# SCH_esp32__2024-09-23.net
KiCad netlist of a schematic drawn in EasyEDA
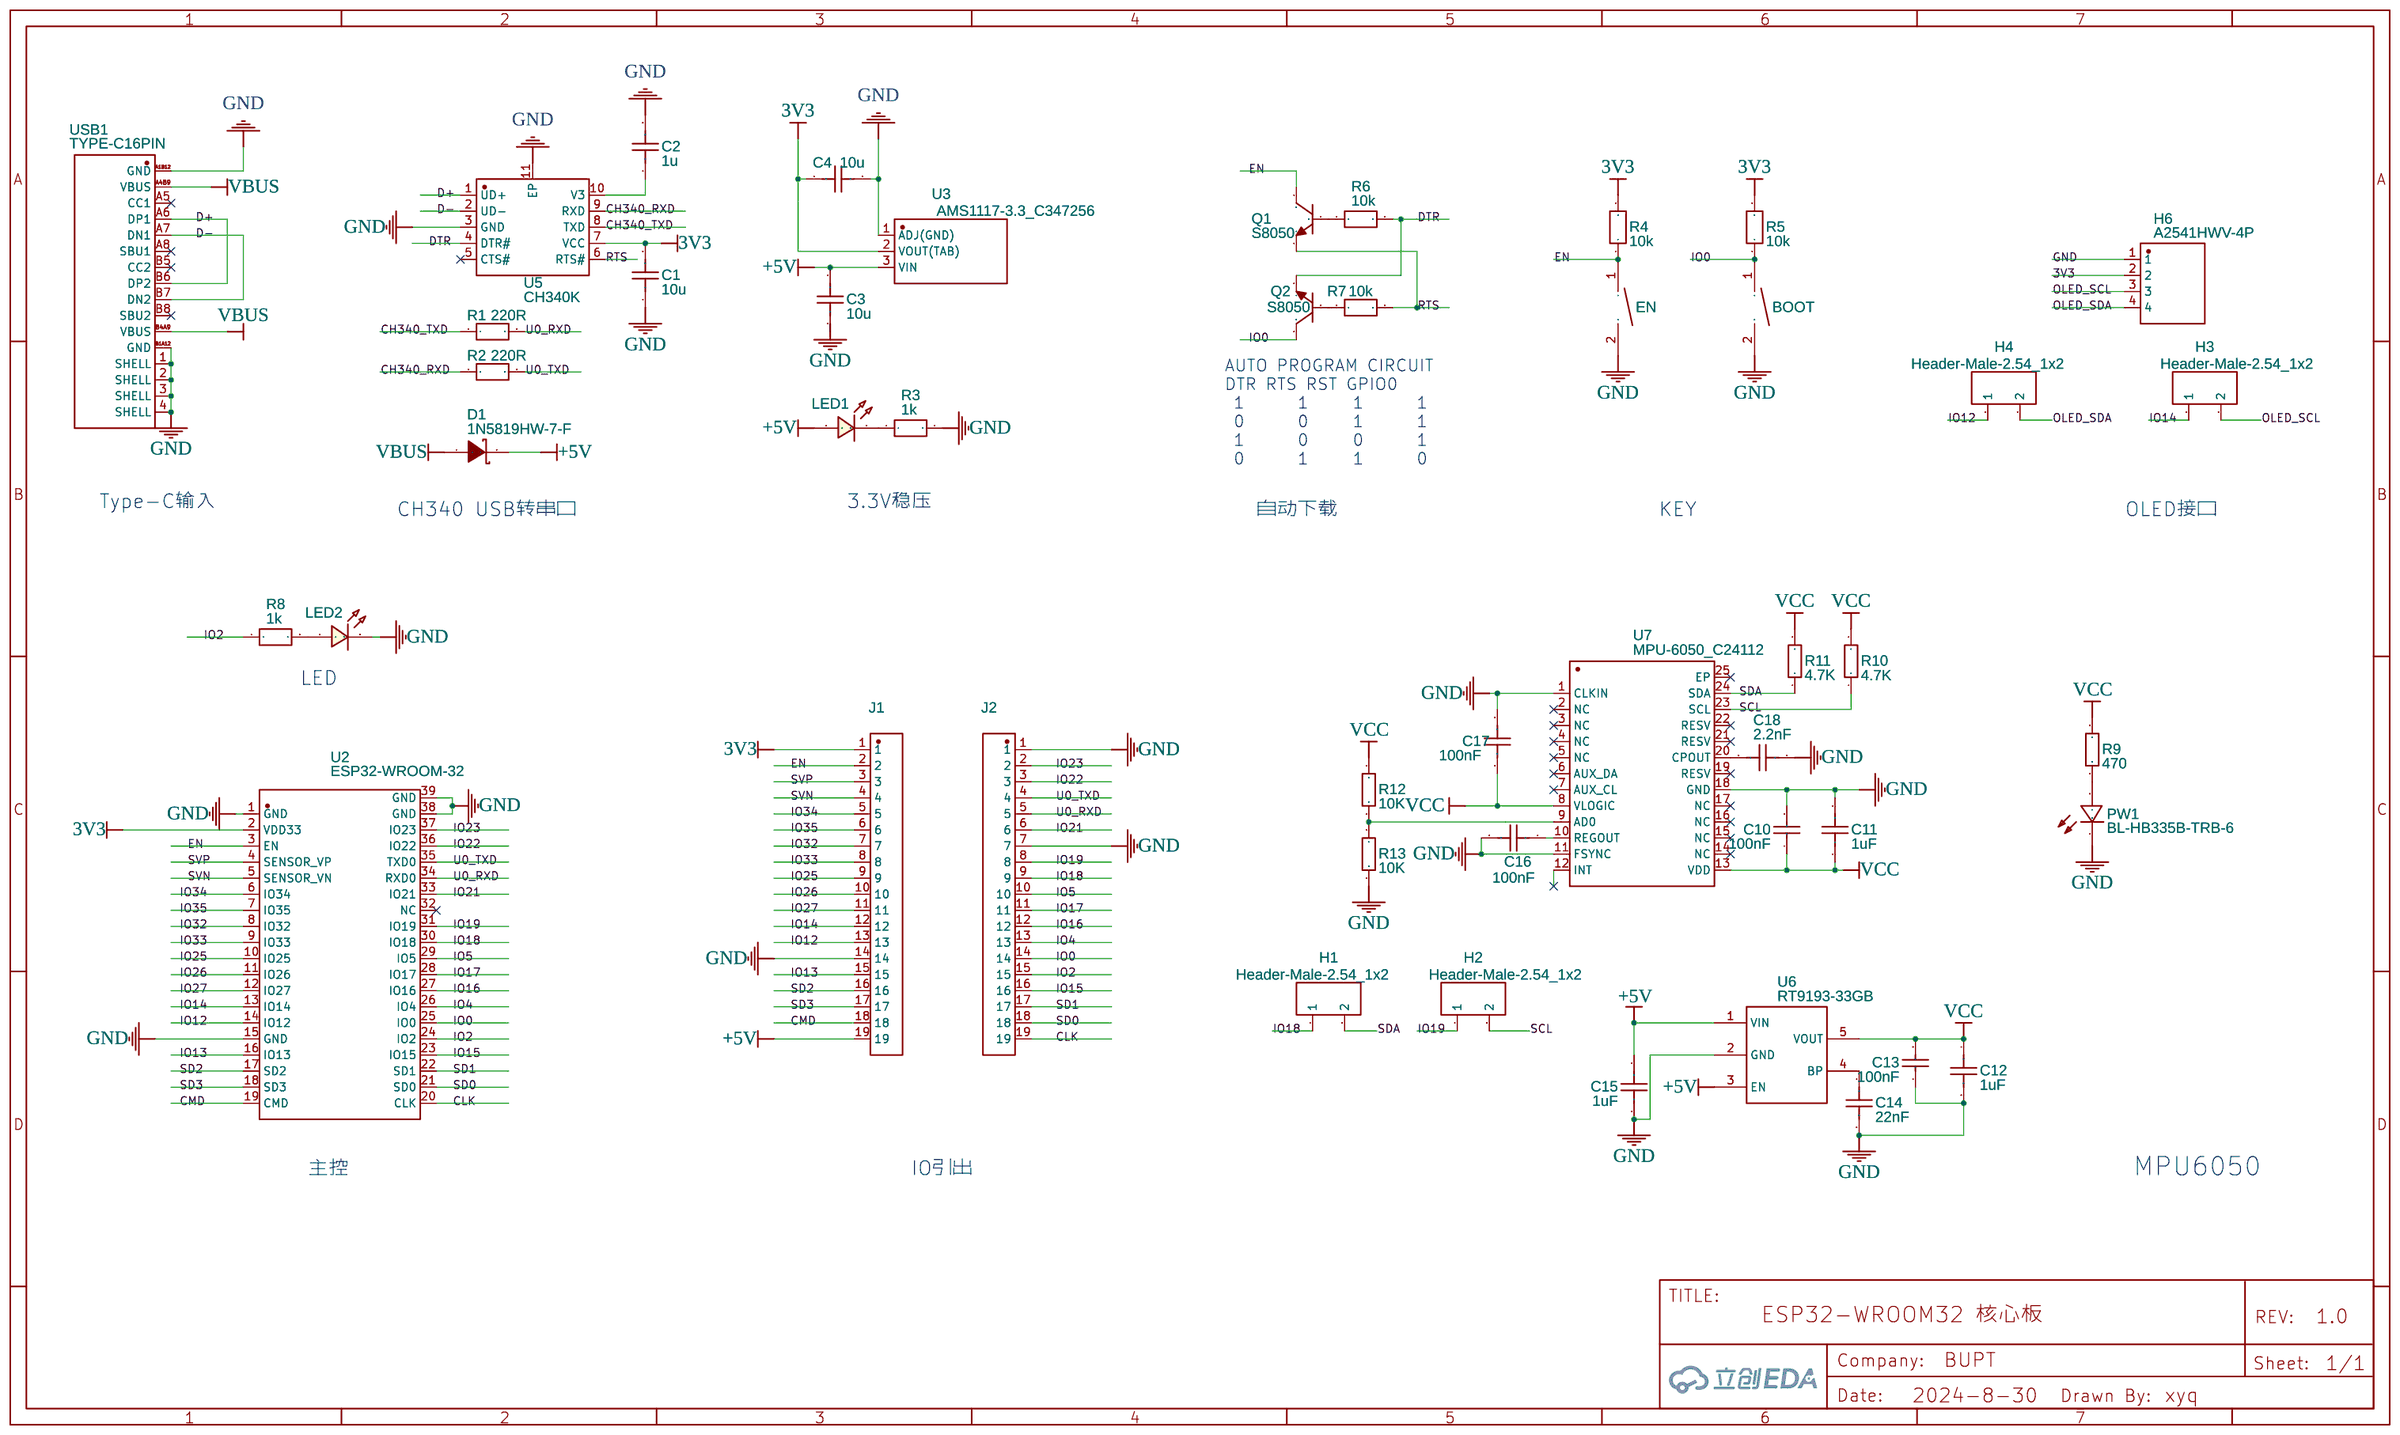
[diagram p0: schematic sheet]

(export (version "E")
  (design (tool "Eeschema 10.0.6"))
  (components
    (comp (ref "BOOT")
      (value "TSA343G00D-250J2")
      (fields (field (name "Manufacturer") "BRIGHT"))
      (libsource (lib "") (part "TSA343G00D-250J2"))
    )
    (comp (ref "C1") (value "10u") (libsource (lib "") (part "C_0603_US_1")))
    (comp (ref "C2") (value "1u") (libsource (lib "") (part "C_0603_US_1")))
    (comp (ref "C3") (value "10u") (libsource (lib "") (part "C_0603_US_2")))
    (comp (ref "C4") (value "10u") (libsource (lib "") (part "C_0603_US")))
    (comp (ref "C10")
      (value "100nF")
      (fields
        (field (name "Manufacturer Part") "CT41G-0603-2X1-50V-0.1μF-K(N)")
        (field (name "Manufacturer") "TORCH")
      )
      (libsource (lib "") (part "CT41G-0603-2X1-50V-0.1μF-K(N)"))
    )
    (comp (ref "C11")
      (value "1uF")
      (fields
        (field (name "Manufacturer Part") "GRM185R61E105KA12D")
        (field (name "Manufacturer") "Murata Electronics")
      )
      (libsource (lib "") (part "GRM185R61E105KA12D_1"))
    )
    (comp (ref "C12")
      (value "1uF")
      (fields
        (field (name "Manufacturer Part") "GRM185R61E105KA12D")
        (field (name "Manufacturer") "Murata Electronics")
      )
      (libsource (lib "") (part "GRM185R61E105KA12D_1"))
    )
    (comp (ref "C13")
      (value "100nF")
      (fields
        (field (name "Manufacturer Part") "CT41G-0603-2X1-50V-0.1μF-K(N)")
        (field (name "Manufacturer") "TORCH")
      )
      (libsource (lib "") (part "CT41G-0603-2X1-50V-0.1μF-K(N)"))
    )
    (comp (ref "C14")
      (value "22nF")
      (fields
        (field (name "Manufacturer Part") "0603B223K500CT")
        (field (name "Manufacturer") "Walsin Tech Corp")
      )
      (libsource (lib "") (part "0603B223K500CT"))
    )
    (comp (ref "C15")
      (value "1uF")
      (fields
        (field (name "Manufacturer Part") "GRM185R61E105KA12D")
        (field (name "Manufacturer") "Murata Electronics")
      )
      (libsource (lib "") (part "GRM185R61E105KA12D"))
    )
    (comp (ref "C16")
      (value "100nF")
      (fields (field (name "Manufacturer Part") "CC0603KRX7R9BB104") (field (name "Manufacturer") "YAGEO"))
      (libsource (lib "") (part "CC0603KRX7R9BB104"))
    )
    (comp (ref "C17")
      (value "100nF")
      (fields (field (name "Manufacturer Part") "CC0603KRX7R9BB104") (field (name "Manufacturer") "YAGEO"))
      (libsource (lib "") (part "CC0603KRX7R9BB104_1"))
    )
    (comp (ref "C18")
      (value "2.2nF")
      (fields (field (name "Manufacturer Part") "CS0603KRX7R9BB222") (field (name "Manufacturer") "YAGEO"))
      (libsource (lib "") (part "CS0603KRX7R9BB222"))
    )
    (comp (ref "D1")
      (value "1N5819HW-7-F")
      (fields (field (name "Manufacturer") "DIODES"))
      (libsource (lib "") (part "1N5819HW-7-F"))
    )
    (comp (ref "EN")
      (value "TSA343G00D-250J2")
      (fields (field (name "Manufacturer") "BRIGHT"))
      (libsource (lib "") (part "TSA343G00D-250J2_1"))
    )
    (comp (ref "H1")
      (value "Header-Male-2.54_1x2")
      (fields (field (name "Manufacturer Part") "826629-2") (field (name "Manufacturer") "TE Connectivity"))
      (libsource (lib "") (part "Header-Male-2.54_1x2"))
    )
    (comp (ref "H2")
      (value "Header-Male-2.54_1x2")
      (fields (field (name "Manufacturer Part") "826629-2") (field (name "Manufacturer") "TE Connectivity"))
      (libsource (lib "") (part "Header-Male-2.54_1x2"))
    )
    (comp (ref "H3")
      (value "Header-Male-2.54_1x2")
      (fields (field (name "Manufacturer Part") "826629-2") (field (name "Manufacturer") "TE Connectivity"))
      (libsource (lib "") (part "Header-Male-2.54_1x2"))
    )
    (comp (ref "H4")
      (value "Header-Male-2.54_1x2")
      (fields (field (name "Manufacturer Part") "826629-2") (field (name "Manufacturer") "TE Connectivity"))
      (libsource (lib "") (part "Header-Male-2.54_1x2"))
    )
    (comp (ref "H6")
      (value "A2541HWV-4P")
      (fields (field (name "Manufacturer") "Changjiang Connectors"))
      (libsource (lib "") (part "A2541HWV-4P"))
    )
    (comp (ref "J1")
      (value "Header-Male-2.54_1x19")
      (fields (field (name "Manufacturer Part") "2.54mm 1*20PHeader") (field (name "Manufacturer") "BOOMELE"))
      (libsource (lib "") (part "Header-Male-2.54_1x19_1"))
    )
    (comp (ref "J2")
      (value "Header-Male-2.54_1x19")
      (fields (field (name "Manufacturer Part") "2.54mm 1*20PHeader") (field (name "Manufacturer") "BOOMELE"))
      (libsource (lib "") (part "Header-Male-2.54_1x19"))
    )
    (comp (ref "LED1")
      (value "LED-0603_R")
      (fields
        (field (name "Manufacturer Part") "19-217/R6C-AL1M2VY/3T")
        (field (name "Manufacturer") "EVERLIGHT(台湾亿光)")
      )
      (libsource (lib "") (part "LED-0603_R"))
    )
    (comp (ref "LED2")
      (value "LED-0603_R")
      (fields
        (field (name "Manufacturer Part") "19-217/R6C-AL1M2VY/3T")
        (field (name "Manufacturer") "EVERLIGHT(台湾亿光)")
      )
      (libsource (lib "") (part "LED-0603_R"))
    )
    (comp (ref "PW1")
      (value "BL-HB335B-TRB-6")
      (fields (field (name "Manufacturer") "Bright LED Elec"))
      (libsource (lib "") (part "BL-HB335B-TRB-6"))
    )
    (comp (ref "Q1")
      (value "S8050")
      (fields (field (name "Manufacturer") "WPMtek(维攀微)"))
      (libsource (lib "") (part "S8050_1"))
    )
    (comp (ref "Q2")
      (value "S8050")
      (fields (field (name "Manufacturer") "WPMtek(维攀微)"))
      (libsource (lib "") (part "S8050"))
    )
    (comp (ref "R1") (value "220R") (libsource (lib "") (part "R_0603_EU")))
    (comp (ref "R2") (value "220R") (libsource (lib "") (part "R_0603_EU")))
    (comp (ref "R3") (value "1k") (libsource (lib "") (part "R_0603_EU")))
    (comp (ref "R4") (value "10k") (libsource (lib "") (part "R_0603_EU_1")))
    (comp (ref "R5") (value "10k") (libsource (lib "") (part "R_0603_EU_1")))
    (comp (ref "R6") (value "10k") (libsource (lib "") (part "R_0603_EU")))
    (comp (ref "R7") (value "10k") (libsource (lib "") (part "R_0603_EU")))
    (comp (ref "R8") (value "1k") (libsource (lib "") (part "R_0603_EU")))
    (comp (ref "R9")
      (value "470")
      (fields (field (name "Manufacturer Part") "CR0805J80471G") (field (name "Manufacturer") "LIZ"))
      (libsource (lib "") (part "CR0805J80471G"))
    )
    (comp (ref "R10")
      (value "4.7K")
      (fields (field (name "Manufacturer Part") "RMC08054.7K1%N") (field (name "Manufacturer") "Tyohm"))
      (libsource (lib "") (part "RMC08054.7K1%N"))
    )
    (comp (ref "R11")
      (value "4.7K")
      (fields (field (name "Manufacturer Part") "RMC08054.7K1%N") (field (name "Manufacturer") "Tyohm"))
      (libsource (lib "") (part "RMC08054.7K1%N"))
    )
    (comp (ref "R12")
      (value "10K")
      (fields (field (name "Manufacturer Part") "WR08X1002FTL") (field (name "Manufacturer") "WTC"))
      (libsource (lib "") (part "WR08X1002FTL"))
    )
    (comp (ref "R13")
      (value "10K")
      (fields (field (name "Manufacturer Part") "WR08X1002FTL") (field (name "Manufacturer") "WTC"))
      (libsource (lib "") (part "WR08X1002FTL"))
    )
    (comp (ref "U2")
      (value "ESP32-WROOM-32")
      (fields (field (name "Manufacturer") "Espressif Systems"))
      (libsource (lib "") (part "ESP32-WROOM-32"))
    )
    (comp (ref "U3")
      (value "AMS1117-3.3_C347256")
      (fields
        (field (name "Manufacturer Part") "AMS1117-3.3")
        (field (name "Manufacturer") "Youtai Semiconductor Co., Ltd.")
      )
      (libsource (lib "") (part "AMS1117-3.3_C347256"))
    )
    (comp (ref "U5")
      (value "CH340K")
      (fields (field (name "Manufacturer") "WCH(Jiangsu Qin Heng)"))
      (libsource (lib "") (part "CH340K"))
    )
    (comp (ref "U6")
      (value "RT9193-33GB")
      (fields (field (name "Manufacturer") "RICHTEK"))
      (libsource (lib "") (part "RT9193-33GB"))
    )
    (comp (ref "U7")
      (value "MPU-6050_C24112")
      (fields (field (name "Manufacturer Part") "MPU-6050") (field (name "Manufacturer") "InvenSense"))
      (libsource (lib "") (part "MPU-6050_C24112"))
    )
    (comp (ref "USB1")
      (value "TYPE-C16PIN")
      (fields (field (name "Manufacturer") "SHOU HAN"))
      (libsource (lib "") (part "TYPE-C16PIN"))
    )
  )
  (nets
    (net (code "1") (name "+5V") (class "Default")
      (node (ref "C15") (pin "1") (pinfunction "1_1") (pintype "unspecified"))
      (node (ref "C3") (pin "1") (pinfunction "1_1") (pintype "unspecified"))
      (node (ref "D1") (pin "2") (pinfunction "K_2") (pintype "unspecified"))
      (node (ref "J1") (pin "19") (pinfunction "19_19") (pintype "unspecified"))
      (node (ref "LED1") (pin "1") (pinfunction "1_1") (pintype "unspecified"))
      (node (ref "U3") (pin "3") (pinfunction "VIN_3") (pintype "unspecified"))
      (node (ref "U6") (pin "1") (pinfunction "VIN_1") (pintype "unspecified"))
      (node (ref "U6") (pin "3") (pinfunction "EN_3") (pintype "unspecified"))
    )
    (net (code "2") (name "/CH340_RXD") (class "Default")
      (node (ref "R2") (pin "1") (pinfunction "1_1") (pintype "unspecified"))
      (node (ref "U5") (pin "9") (pinfunction "RXD_9") (pintype "unspecified"))
    )
    (net (code "3") (name "/CH340_TXD") (class "Default")
      (node (ref "R1") (pin "1") (pinfunction "1_1") (pintype "unspecified"))
      (node (ref "U5") (pin "8") (pinfunction "TXD_8") (pintype "unspecified"))
    )
    (net (code "4") (name "/CLK") (class "Default")
      (node (ref "J2") (pin "19") (pinfunction "19_19") (pintype "unspecified"))
      (node (ref "U2") (pin "20") (pinfunction "CLK_20") (pintype "unspecified"))
    )
    (net (code "5") (name "/CMD") (class "Default")
      (node (ref "J1") (pin "18") (pinfunction "18_18") (pintype "unspecified"))
      (node (ref "U2") (pin "19") (pinfunction "CMD_19") (pintype "unspecified"))
    )
    (net (code "6") (name "/D+") (class "Default")
      (node (ref "U5") (pin "1") (pinfunction "UD+_1") (pintype "unspecified"))
      (node (ref "USB1") (pin "A6") (pinfunction "DP1_A6") (pintype "unspecified"))
      (node (ref "USB1") (pin "B6") (pinfunction "DP2_B6") (pintype "unspecified"))
    )
    (net (code "7") (name "/D-") (class "Default")
      (node (ref "U5") (pin "2") (pinfunction "UD-_2") (pintype "unspecified"))
      (node (ref "USB1") (pin "A7") (pinfunction "DN1_A7") (pintype "unspecified"))
      (node (ref "USB1") (pin "B7") (pinfunction "DN2_B7") (pintype "unspecified"))
    )
    (net (code "8") (name "/DTR") (class "Default")
      (node (ref "Q2") (pin "2") (pinfunction "E_2") (pintype "input"))
      (node (ref "R6") (pin "2") (pinfunction "2_2") (pintype "unspecified"))
      (node (ref "U5") (pin "4") (pinfunction "DTR#_4") (pintype "unspecified"))
    )
    (net (code "9") (name "/EN") (class "Default")
      (node (ref "EN") (pin "1") (pinfunction "1_1") (pintype "input"))
      (node (ref "J1") (pin "2") (pinfunction "2_2") (pintype "unspecified"))
      (node (ref "Q1") (pin "3") (pinfunction "C_3") (pintype "input"))
      (node (ref "R4") (pin "1") (pinfunction "1_1") (pintype "unspecified"))
      (node (ref "U2") (pin "3") (pinfunction "EN_3") (pintype "unspecified"))
    )
    (net (code "10") (name "/IO0") (class "Default")
      (node (ref "BOOT") (pin "1") (pinfunction "1_1") (pintype "input"))
      (node (ref "J2") (pin "14") (pinfunction "14_14") (pintype "unspecified"))
      (node (ref "Q2") (pin "3") (pinfunction "C_3") (pintype "input"))
      (node (ref "R5") (pin "1") (pinfunction "1_1") (pintype "unspecified"))
      (node (ref "U2") (pin "25") (pinfunction "IO0_25") (pintype "unspecified"))
    )
    (net (code "11") (name "/IO2") (class "Default")
      (node (ref "J2") (pin "15") (pinfunction "15_15") (pintype "unspecified"))
      (node (ref "R8") (pin "1") (pinfunction "1_1") (pintype "unspecified"))
      (node (ref "U2") (pin "24") (pinfunction "IO2_24") (pintype "unspecified"))
    )
    (net (code "12") (name "/IO4") (class "Default")
      (node (ref "J2") (pin "13") (pinfunction "13_13") (pintype "unspecified"))
      (node (ref "U2") (pin "26") (pinfunction "IO4_26") (pintype "unspecified"))
    )
    (net (code "13") (name "/IO5") (class "Default")
      (node (ref "J2") (pin "10") (pinfunction "10_10") (pintype "unspecified"))
      (node (ref "U2") (pin "29") (pinfunction "IO5_29") (pintype "unspecified"))
    )
    (net (code "14") (name "/IO12") (class "Default")
      (node (ref "H4") (pin "1") (pinfunction "1_1") (pintype "unspecified"))
      (node (ref "J1") (pin "13") (pinfunction "13_13") (pintype "unspecified"))
      (node (ref "U2") (pin "14") (pinfunction "IO12_14") (pintype "unspecified"))
    )
    (net (code "15") (name "/IO13") (class "Default")
      (node (ref "J1") (pin "15") (pinfunction "15_15") (pintype "unspecified"))
      (node (ref "U2") (pin "16") (pinfunction "IO13_16") (pintype "unspecified"))
    )
    (net (code "16") (name "/IO14") (class "Default")
      (node (ref "H3") (pin "1") (pinfunction "1_1") (pintype "unspecified"))
      (node (ref "J1") (pin "12") (pinfunction "12_12") (pintype "unspecified"))
      (node (ref "U2") (pin "13") (pinfunction "IO14_13") (pintype "unspecified"))
    )
    (net (code "17") (name "/IO15") (class "Default")
      (node (ref "J2") (pin "16") (pinfunction "16_16") (pintype "unspecified"))
      (node (ref "U2") (pin "23") (pinfunction "IO15_23") (pintype "unspecified"))
    )
    (net (code "18") (name "/IO16") (class "Default")
      (node (ref "J2") (pin "12") (pinfunction "12_12") (pintype "unspecified"))
      (node (ref "U2") (pin "27") (pinfunction "IO16_27") (pintype "unspecified"))
    )
    (net (code "19") (name "/IO17") (class "Default")
      (node (ref "J2") (pin "11") (pinfunction "11_11") (pintype "unspecified"))
      (node (ref "U2") (pin "28") (pinfunction "IO17_28") (pintype "unspecified"))
    )
    (net (code "20") (name "/IO18") (class "Default")
      (node (ref "H1") (pin "1") (pinfunction "1_1") (pintype "unspecified"))
      (node (ref "J2") (pin "9") (pinfunction "9_9") (pintype "unspecified"))
      (node (ref "U2") (pin "30") (pinfunction "IO18_30") (pintype "unspecified"))
    )
    (net (code "21") (name "/IO19") (class "Default")
      (node (ref "H2") (pin "1") (pinfunction "1_1") (pintype "unspecified"))
      (node (ref "J2") (pin "8") (pinfunction "8_8") (pintype "unspecified"))
      (node (ref "U2") (pin "31") (pinfunction "IO19_31") (pintype "unspecified"))
    )
    (net (code "22") (name "/IO21") (class "Default")
      (node (ref "J2") (pin "6") (pinfunction "6_6") (pintype "unspecified"))
      (node (ref "U2") (pin "33") (pinfunction "IO21_33") (pintype "unspecified"))
    )
    (net (code "23") (name "/IO22") (class "Default")
      (node (ref "J2") (pin "3") (pinfunction "3_3") (pintype "unspecified"))
      (node (ref "U2") (pin "36") (pinfunction "IO22_36") (pintype "unspecified"))
    )
    (net (code "24") (name "/IO23") (class "Default")
      (node (ref "J2") (pin "2") (pinfunction "2_2") (pintype "unspecified"))
      (node (ref "U2") (pin "37") (pinfunction "IO23_37") (pintype "unspecified"))
    )
    (net (code "25") (name "/IO25") (class "Default")
      (node (ref "J1") (pin "9") (pinfunction "9_9") (pintype "unspecified"))
      (node (ref "U2") (pin "10") (pinfunction "IO25_10") (pintype "unspecified"))
    )
    (net (code "26") (name "/IO26") (class "Default")
      (node (ref "J1") (pin "10") (pinfunction "10_10") (pintype "unspecified"))
      (node (ref "U2") (pin "11") (pinfunction "IO26_11") (pintype "unspecified"))
    )
    (net (code "27") (name "/IO27") (class "Default")
      (node (ref "J1") (pin "11") (pinfunction "11_11") (pintype "unspecified"))
      (node (ref "U2") (pin "12") (pinfunction "IO27_12") (pintype "unspecified"))
    )
    (net (code "28") (name "/IO32") (class "Default")
      (node (ref "J1") (pin "7") (pinfunction "7_7") (pintype "unspecified"))
      (node (ref "U2") (pin "8") (pinfunction "IO32_8") (pintype "unspecified"))
    )
    (net (code "29") (name "/IO33") (class "Default")
      (node (ref "J1") (pin "8") (pinfunction "8_8") (pintype "unspecified"))
      (node (ref "U2") (pin "9") (pinfunction "IO33_9") (pintype "unspecified"))
    )
    (net (code "30") (name "/IO34") (class "Default")
      (node (ref "J1") (pin "5") (pinfunction "5_5") (pintype "unspecified"))
      (node (ref "U2") (pin "6") (pinfunction "IO34_6") (pintype "unspecified"))
    )
    (net (code "31") (name "/IO35") (class "Default")
      (node (ref "J1") (pin "6") (pinfunction "6_6") (pintype "unspecified"))
      (node (ref "U2") (pin "7") (pinfunction "IO35_7") (pintype "unspecified"))
    )
    (net (code "32") (name "/OLED_SCL") (class "Default")
      (node (ref "H3") (pin "2") (pinfunction "2_2") (pintype "unspecified"))
      (node (ref "H6") (pin "3") (pinfunction "3_3") (pintype "unspecified"))
    )
    (net (code "33") (name "/OLED_SDA") (class "Default")
      (node (ref "H4") (pin "2") (pinfunction "2_2") (pintype "unspecified"))
      (node (ref "H6") (pin "4") (pinfunction "4_4") (pintype "unspecified"))
    )
    (net (code "34") (name "/RTS") (class "Default")
      (node (ref "Q1") (pin "2") (pinfunction "E_2") (pintype "input"))
      (node (ref "R7") (pin "2") (pinfunction "2_2") (pintype "unspecified"))
      (node (ref "U5") (pin "6") (pinfunction "RTS#_6") (pintype "unspecified"))
    )
    (net (code "35") (name "/SCL") (class "Default")
      (node (ref "H2") (pin "2") (pinfunction "2_2") (pintype "unspecified"))
      (node (ref "R10") (pin "1") (pinfunction "1_1") (pintype "unspecified"))
      (node (ref "U7") (pin "23") (pinfunction "SCL_23") (pintype "unspecified"))
    )
    (net (code "36") (name "/SD0") (class "Default")
      (node (ref "J2") (pin "18") (pinfunction "18_18") (pintype "unspecified"))
      (node (ref "U2") (pin "21") (pinfunction "SD0_21") (pintype "unspecified"))
    )
    (net (code "37") (name "/SD1") (class "Default")
      (node (ref "J2") (pin "17") (pinfunction "17_17") (pintype "unspecified"))
      (node (ref "U2") (pin "22") (pinfunction "SD1_22") (pintype "unspecified"))
    )
    (net (code "38") (name "/SD2") (class "Default")
      (node (ref "J1") (pin "16") (pinfunction "16_16") (pintype "unspecified"))
      (node (ref "U2") (pin "17") (pinfunction "SD2_17") (pintype "unspecified"))
    )
    (net (code "39") (name "/SD3") (class "Default")
      (node (ref "J1") (pin "17") (pinfunction "17_17") (pintype "unspecified"))
      (node (ref "U2") (pin "18") (pinfunction "SD3_18") (pintype "unspecified"))
    )
    (net (code "40") (name "/SDA") (class "Default")
      (node (ref "H1") (pin "2") (pinfunction "2_2") (pintype "unspecified"))
      (node (ref "R11") (pin "1") (pinfunction "1_1") (pintype "unspecified"))
      (node (ref "U7") (pin "24") (pinfunction "SDA_24") (pintype "unspecified"))
    )
    (net (code "41") (name "/SVN") (class "Default")
      (node (ref "J1") (pin "4") (pinfunction "4_4") (pintype "unspecified"))
      (node (ref "U2") (pin "5") (pinfunction "SENSOR_VN_5") (pintype "unspecified"))
    )
    (net (code "42") (name "/SVP") (class "Default")
      (node (ref "J1") (pin "3") (pinfunction "3_3") (pintype "unspecified"))
      (node (ref "U2") (pin "4") (pinfunction "SENSOR_VP_4") (pintype "unspecified"))
    )
    (net (code "43") (name "/U0_RXD") (class "Default")
      (node (ref "J2") (pin "5") (pinfunction "5_5") (pintype "unspecified"))
      (node (ref "R1") (pin "2") (pinfunction "2_2") (pintype "unspecified"))
      (node (ref "U2") (pin "34") (pinfunction "RXD0_34") (pintype "unspecified"))
    )
    (net (code "44") (name "/U0_TXD") (class "Default")
      (node (ref "J2") (pin "4") (pinfunction "4_4") (pintype "unspecified"))
      (node (ref "R2") (pin "2") (pinfunction "2_2") (pintype "unspecified"))
      (node (ref "U2") (pin "35") (pinfunction "TXD0_35") (pintype "unspecified"))
    )
    (net (code "45") (name "3V3") (class "Default")
      (node (ref "C1") (pin "2") (pinfunction "2_2") (pintype "unspecified"))
      (node (ref "C4") (pin "1") (pinfunction "1_1") (pintype "unspecified"))
      (node (ref "H6") (pin "2") (pinfunction "2_2") (pintype "unspecified"))
      (node (ref "J1") (pin "1") (pinfunction "1_1") (pintype "unspecified"))
      (node (ref "R4") (pin "2") (pinfunction "2_2") (pintype "unspecified"))
      (node (ref "R5") (pin "2") (pinfunction "2_2") (pintype "unspecified"))
      (node (ref "U2") (pin "2") (pinfunction "VDD33_2") (pintype "unspecified"))
      (node (ref "U3") (pin "2") (pinfunction "VOUT(TAB)_2") (pintype "unspecified"))
      (node (ref "U5") (pin "7") (pinfunction "VCC_7") (pintype "unspecified"))
    )
    (net (code "46") (name "GND") (class "Default")
      (node (ref "BOOT") (pin "2") (pinfunction "2_2") (pintype "input"))
      (node (ref "C1") (pin "1") (pinfunction "1_1") (pintype "unspecified"))
      (node (ref "C10") (pin "2") (pinfunction "2_2") (pintype "input"))
      (node (ref "C11") (pin "1") (pinfunction "1_1") (pintype "unspecified"))
      (node (ref "C12") (pin "2") (pinfunction "2_2") (pintype "unspecified"))
      (node (ref "C13") (pin "1") (pinfunction "1_1") (pintype "input"))
      (node (ref "C14") (pin "2") (pinfunction "2_2") (pintype "unspecified"))
      (node (ref "C15") (pin "2") (pinfunction "2_2") (pintype "unspecified"))
      (node (ref "C16") (pin "2") (pinfunction "2_2") (pintype "unspecified"))
      (node (ref "C17") (pin "2") (pinfunction "2_2") (pintype "unspecified"))
      (node (ref "C18") (pin "1") (pinfunction "1_1") (pintype "unspecified"))
      (node (ref "C2") (pin "2") (pinfunction "2_2") (pintype "unspecified"))
      (node (ref "C3") (pin "2") (pinfunction "2_2") (pintype "unspecified"))
      (node (ref "C4") (pin "2") (pinfunction "2_2") (pintype "unspecified"))
      (node (ref "EN") (pin "2") (pinfunction "2_2") (pintype "input"))
      (node (ref "H6") (pin "1") (pinfunction "1_1") (pintype "unspecified"))
      (node (ref "J1") (pin "14") (pinfunction "14_14") (pintype "unspecified"))
      (node (ref "J2") (pin "1") (pinfunction "1_1") (pintype "unspecified"))
      (node (ref "J2") (pin "7") (pinfunction "7_7") (pintype "unspecified"))
      (node (ref "LED2") (pin "2") (pinfunction "2_2") (pintype "unspecified"))
      (node (ref "PW1") (pin "1") (pinfunction "C_1") (pintype "unspecified"))
      (node (ref "R13") (pin "2") (pinfunction "2_2") (pintype "input"))
      (node (ref "R3") (pin "2") (pinfunction "2_2") (pintype "unspecified"))
      (node (ref "U2") (pin "1") (pinfunction "GND_1") (pintype "unspecified"))
      (node (ref "U2") (pin "15") (pinfunction "GND_15") (pintype "unspecified"))
      (node (ref "U2") (pin "38") (pinfunction "GND_38") (pintype "unspecified"))
      (node (ref "U2") (pin "39") (pinfunction "GND_39") (pintype "unspecified"))
      (node (ref "U3") (pin "1") (pinfunction "ADJ(GND)_1") (pintype "unspecified"))
      (node (ref "U5") (pin "11") (pinfunction "EP_11") (pintype "unspecified"))
      (node (ref "U5") (pin "3") (pinfunction "GND_3") (pintype "unspecified"))
      (node (ref "U6") (pin "2") (pinfunction "GND_2") (pintype "unspecified"))
      (node (ref "U7") (pin "1") (pinfunction "CLKIN_1") (pintype "unspecified"))
      (node (ref "U7") (pin "11") (pinfunction "FSYNC_11") (pintype "unspecified"))
      (node (ref "U7") (pin "18") (pinfunction "GND_18") (pintype "unspecified"))
      (node (ref "USB1") (pin "1") (pinfunction "SHELL_1") (pintype "unspecified"))
      (node (ref "USB1") (pin "2") (pinfunction "SHELL_2") (pintype "unspecified"))
      (node (ref "USB1") (pin "3") (pinfunction "SHELL_3") (pintype "unspecified"))
      (node (ref "USB1") (pin "4") (pinfunction "SHELL_4") (pintype "unspecified"))
      (node (ref "USB1") (pin "A1B12") (pinfunction "GND_A1B12") (pintype "unspecified"))
      (node (ref "USB1") (pin "B1A12") (pinfunction "GND_B1A12") (pintype "unspecified"))
    )
    (net (code "47") (name "Net-(LED1-Pad2)") (class "Default")
      (node (ref "LED1") (pin "2") (pinfunction "2_2") (pintype "unspecified"))
      (node (ref "R3") (pin "1") (pinfunction "1_1") (pintype "unspecified"))
    )
    (net (code "48") (name "Net-(LED2-Pad1)") (class "Default")
      (node (ref "LED2") (pin "1") (pinfunction "1_1") (pintype "unspecified"))
      (node (ref "R8") (pin "2") (pinfunction "2_2") (pintype "unspecified"))
    )
    (net (code "49") (name "Net-(PW1-A)") (class "Default")
      (node (ref "PW1") (pin "2") (pinfunction "A_2") (pintype "unspecified"))
      (node (ref "R9") (pin "1") (pinfunction "1_1") (pintype "input"))
    )
    (net (code "50") (name "Net-(Q1-B)") (class "Default")
      (node (ref "Q1") (pin "1") (pinfunction "B_1") (pintype "input"))
      (node (ref "R6") (pin "1") (pinfunction "1_1") (pintype "unspecified"))
    )
    (net (code "51") (name "Net-(Q2-B)") (class "Default")
      (node (ref "Q2") (pin "1") (pinfunction "B_1") (pintype "input"))
      (node (ref "R7") (pin "1") (pinfunction "1_1") (pintype "unspecified"))
    )
    (net (code "52") (name "Net-(U5-V3)") (class "Default")
      (node (ref "C2") (pin "1") (pinfunction "1_1") (pintype "unspecified"))
      (node (ref "U5") (pin "10") (pinfunction "V3_10") (pintype "unspecified"))
    )
    (net (code "53") (name "Net-(U6-BP)") (class "Default")
      (node (ref "C14") (pin "1") (pinfunction "1_1") (pintype "unspecified"))
      (node (ref "U6") (pin "4") (pinfunction "BP_4") (pintype "unspecified"))
    )
    (net (code "54") (name "Net-(U7-AD0)") (class "Default")
      (node (ref "R12") (pin "2") (pinfunction "2_2") (pintype "input"))
      (node (ref "R13") (pin "1") (pinfunction "1_1") (pintype "input"))
      (node (ref "U7") (pin "9") (pinfunction "AD0_9") (pintype "unspecified"))
    )
    (net (code "55") (name "Net-(U7-CPOUT)") (class "Default")
      (node (ref "C18") (pin "2") (pinfunction "2_2") (pintype "unspecified"))
      (node (ref "U7") (pin "20") (pinfunction "CPOUT_20") (pintype "unspecified"))
    )
    (net (code "56") (name "Net-(U7-REGOUT)") (class "Default")
      (node (ref "C16") (pin "1") (pinfunction "1_1") (pintype "unspecified"))
      (node (ref "U7") (pin "10") (pinfunction "REGOUT_10") (pintype "unspecified"))
    )
    (net (code "57") (name "VBUS") (class "Default")
      (node (ref "D1") (pin "1") (pinfunction "A_1") (pintype "unspecified"))
      (node (ref "USB1") (pin "A4B9") (pinfunction "VBUS_A4B9") (pintype "unspecified"))
      (node (ref "USB1") (pin "B4A9") (pinfunction "VBUS_B4A9") (pintype "unspecified"))
    )
    (net (code "58") (name "VCC") (class "Default")
      (node (ref "C10") (pin "1") (pinfunction "1_1") (pintype "input"))
      (node (ref "C11") (pin "2") (pinfunction "2_2") (pintype "unspecified"))
      (node (ref "C12") (pin "1") (pinfunction "1_1") (pintype "unspecified"))
      (node (ref "C13") (pin "2") (pinfunction "2_2") (pintype "input"))
      (node (ref "C17") (pin "1") (pinfunction "1_1") (pintype "unspecified"))
      (node (ref "R10") (pin "2") (pinfunction "2_2") (pintype "unspecified"))
      (node (ref "R11") (pin "2") (pinfunction "2_2") (pintype "unspecified"))
      (node (ref "R12") (pin "1") (pinfunction "1_1") (pintype "input"))
      (node (ref "R9") (pin "2") (pinfunction "2_2") (pintype "input"))
      (node (ref "U6") (pin "5") (pinfunction "VOUT_5") (pintype "unspecified"))
      (node (ref "U7") (pin "13") (pinfunction "VDD_13") (pintype "unspecified"))
      (node (ref "U7") (pin "8") (pinfunction "VLOGIC_8") (pintype "unspecified"))
    )
    (net (code "59") (name "unconnected-(U2-NC-Pad32)") (class "Default")
      (node (ref "U2") (pin "32") (pinfunction "NC_32") (pintype "unspecified+no_connect"))
    )
    (net (code "60") (name "unconnected-(U5-CTS#-Pad5)") (class "Default")
      (node (ref "U5") (pin "5") (pinfunction "CTS#_5") (pintype "unspecified+no_connect"))
    )
    (net (code "61") (name "unconnected-(U7-AUX_CL-Pad7)") (class "Default")
      (node (ref "U7") (pin "7") (pinfunction "AUX_CL_7") (pintype "unspecified+no_connect"))
    )
    (net (code "62") (name "unconnected-(U7-AUX_DA-Pad6)") (class "Default")
      (node (ref "U7") (pin "6") (pinfunction "AUX_DA_6") (pintype "unspecified+no_connect"))
    )
    (net (code "63") (name "unconnected-(U7-EP-Pad25)") (class "Default")
      (node (ref "U7") (pin "25") (pinfunction "EP_25") (pintype "unspecified+no_connect"))
    )
    (net (code "64") (name "unconnected-(U7-INT-Pad12)") (class "Default")
      (node (ref "U7") (pin "12") (pinfunction "INT_12") (pintype "unspecified+no_connect"))
    )
    (net (code "65") (name "unconnected-(U7-NC-Pad2)") (class "Default")
      (node (ref "U7") (pin "2") (pinfunction "NC_2") (pintype "unspecified+no_connect"))
    )
    (net (code "66") (name "unconnected-(U7-NC-Pad3)") (class "Default")
      (node (ref "U7") (pin "3") (pinfunction "NC_3") (pintype "unspecified+no_connect"))
    )
    (net (code "67") (name "unconnected-(U7-NC-Pad4)") (class "Default")
      (node (ref "U7") (pin "4") (pinfunction "NC_4") (pintype "unspecified+no_connect"))
    )
    (net (code "68") (name "unconnected-(U7-NC-Pad5)") (class "Default")
      (node (ref "U7") (pin "5") (pinfunction "NC_5") (pintype "unspecified+no_connect"))
    )
    (net (code "69") (name "unconnected-(U7-NC-Pad14)") (class "Default")
      (node (ref "U7") (pin "14") (pinfunction "NC_14") (pintype "unspecified+no_connect"))
    )
    (net (code "70") (name "unconnected-(U7-NC-Pad15)") (class "Default")
      (node (ref "U7") (pin "15") (pinfunction "NC_15") (pintype "unspecified+no_connect"))
    )
    (net (code "71") (name "unconnected-(U7-NC-Pad16)") (class "Default")
      (node (ref "U7") (pin "16") (pinfunction "NC_16") (pintype "unspecified+no_connect"))
    )
    (net (code "72") (name "unconnected-(U7-NC-Pad17)") (class "Default")
      (node (ref "U7") (pin "17") (pinfunction "NC_17") (pintype "unspecified+no_connect"))
    )
    (net (code "73") (name "unconnected-(U7-RESV-Pad19)") (class "Default")
      (node (ref "U7") (pin "19") (pinfunction "RESV_19") (pintype "unspecified+no_connect"))
    )
    (net (code "74") (name "unconnected-(U7-RESV-Pad21)") (class "Default")
      (node (ref "U7") (pin "21") (pinfunction "RESV_21") (pintype "unspecified+no_connect"))
    )
    (net (code "75") (name "unconnected-(U7-RESV-Pad22)") (class "Default")
      (node (ref "U7") (pin "22") (pinfunction "RESV_22") (pintype "unspecified+no_connect"))
    )
    (net (code "76") (name "unconnected-(USB1-CC1-PadA5)") (class "Default")
      (node (ref "USB1") (pin "A5") (pinfunction "CC1_A5") (pintype "unspecified+no_connect"))
    )
    (net (code "77") (name "unconnected-(USB1-CC2-PadB5)") (class "Default")
      (node (ref "USB1") (pin "B5") (pinfunction "CC2_B5") (pintype "unspecified+no_connect"))
    )
    (net (code "78") (name "unconnected-(USB1-SBU1-PadA8)") (class "Default")
      (node (ref "USB1") (pin "A8") (pinfunction "SBU1_A8") (pintype "unspecified+no_connect"))
    )
    (net (code "79") (name "unconnected-(USB1-SBU2-PadB8)") (class "Default")
      (node (ref "USB1") (pin "B8") (pinfunction "SBU2_B8") (pintype "unspecified+no_connect"))
    )
  )
)
